# Placa_Base_Blue_Pill.net
KiCad netlist of a schematic drawn in Altium Designer
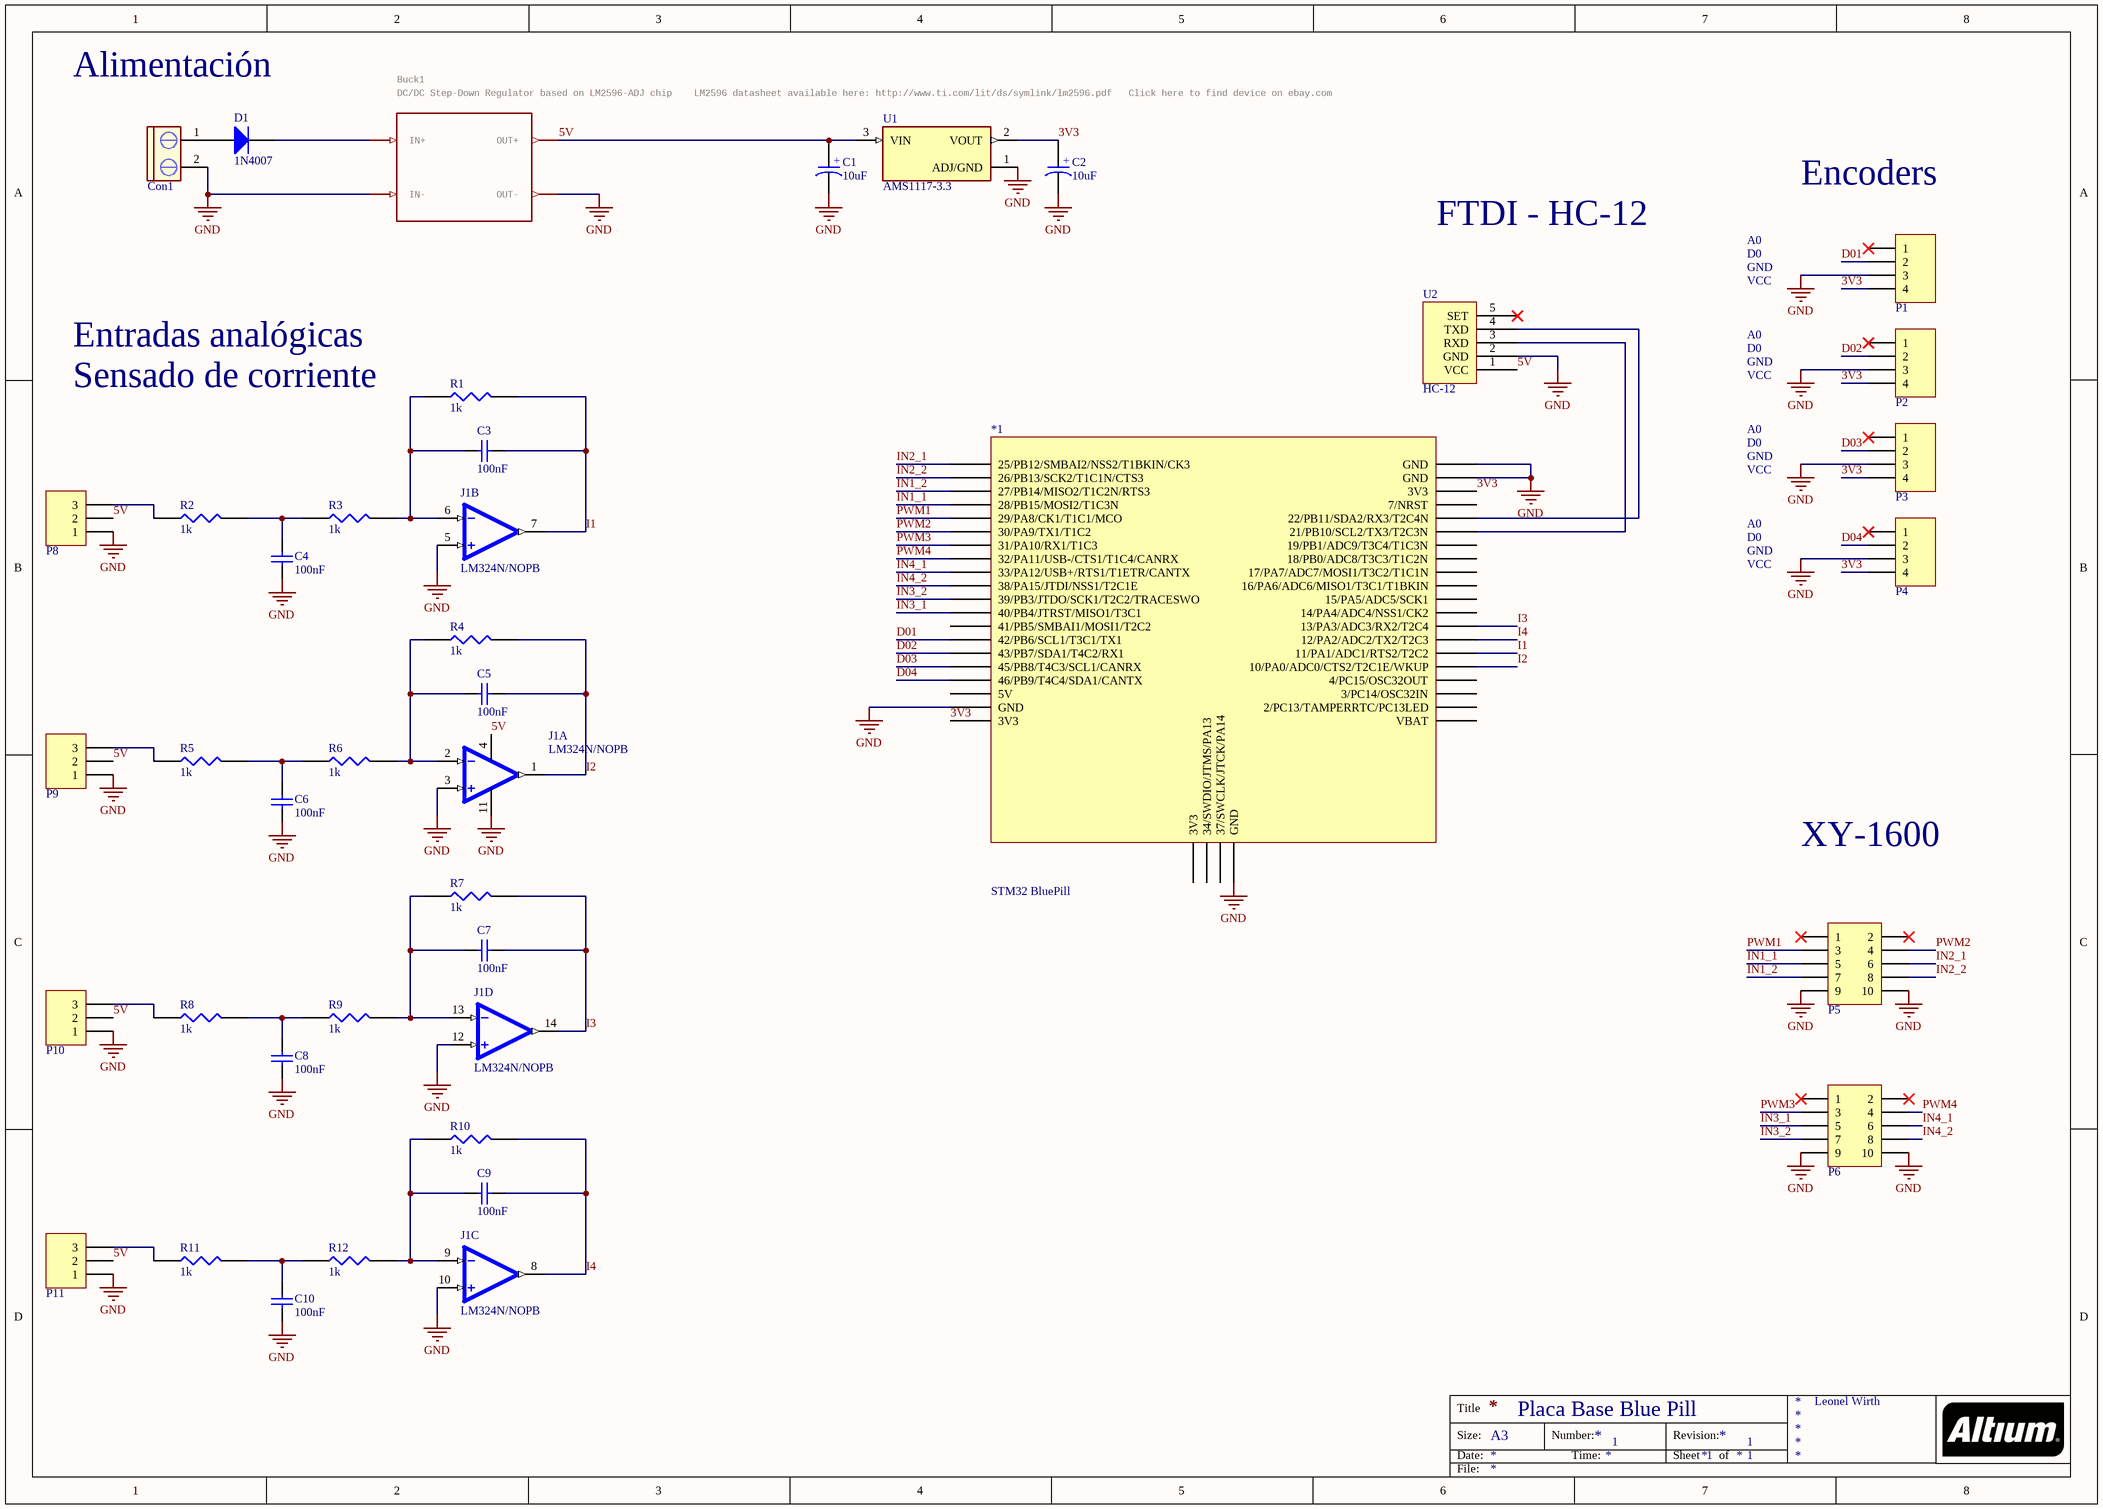
[diagram p0: Placa Base Blue Pill.SchDoc]

(export (version "E")
  (design (tool "Eeschema 10.0.6"))
  (components
    (comp (ref "*1")
      (value "STM32 BluePill")
      (footprint "STM32 BluePill")
      (libsource (lib "LeoLib2.0") (part "STM32 BluePill"))
    )
    (comp (ref "Buck1")
      (value "DC/DC Step-Down Regulator based on LM2596-ADJ chip    LM2596 datasheet available here: http://www.ti.com/lit/ds/symlink/lm2596.pdf   Click here to find device on ebay.com")
      (footprint "DC-DC-STEP-DOWN-LM2596")
      (description "Step Down")
      (libsource (lib "LeoLib2.0") (part "DC-DC-STEP-DOWN-LM2596"))
    )
    (comp (ref "C1")
      (value "10uF")
      (footprint "CAPRADIAL 6.3X11 - 10u")
      (description "CAP_AXIAL")
      (fields (field (name "Comment") "CAP- ELECT"))
      (libsource (lib "LeoLib2.0") (part "Capacitor Electrolitico"))
    )
    (comp (ref "C2")
      (value "10uF")
      (footprint "CAPRADIAL 6.3X11 - 10u")
      (description "CAP_AXIAL")
      (fields (field (name "Comment") "CAP- ELECT"))
      (libsource (lib "LeoLib2.0") (part "Capacitor Electrolitico"))
    )
    (comp (ref "C3")
      (value "100nF")
      (footprint "CAP - LENTEJA")
      (description "CAP-100nf")
      (fields (field (name "Comment") "Cap"))
      (libsource (lib "LeoLib2.0") (part "Capacitor Ceramico"))
    )
    (comp (ref "C4")
      (value "100nF")
      (footprint "CAP - LENTEJA")
      (description "CAP-100nf")
      (fields (field (name "Comment") "Cap"))
      (libsource (lib "LeoLib2.0") (part "Capacitor Ceramico"))
    )
    (comp (ref "C5")
      (value "100nF")
      (footprint "CAP - LENTEJA")
      (description "CAP-100nf")
      (fields (field (name "Comment") "Cap"))
      (libsource (lib "LeoLib2.0") (part "Capacitor Ceramico"))
    )
    (comp (ref "C6")
      (value "100nF")
      (footprint "CAP - LENTEJA")
      (description "CAP-100nf")
      (fields (field (name "Comment") "Cap"))
      (libsource (lib "LeoLib2.0") (part "Capacitor Ceramico"))
    )
    (comp (ref "C7")
      (value "100nF")
      (footprint "CAP - LENTEJA")
      (description "CAP-100nf")
      (fields (field (name "Comment") "Cap"))
      (libsource (lib "LeoLib2.0") (part "Capacitor Ceramico"))
    )
    (comp (ref "C8")
      (value "100nF")
      (footprint "CAP - LENTEJA")
      (description "CAP-100nf")
      (fields (field (name "Comment") "Cap"))
      (libsource (lib "LeoLib2.0") (part "Capacitor Ceramico"))
    )
    (comp (ref "C9")
      (value "100nF")
      (footprint "CAP - LENTEJA")
      (description "CAP-100nf")
      (fields (field (name "Comment") "Cap"))
      (libsource (lib "LeoLib2.0") (part "Capacitor Ceramico"))
    )
    (comp (ref "C10")
      (value "100nF")
      (footprint "CAP - LENTEJA")
      (description "CAP-100nf")
      (fields (field (name "Comment") "Cap"))
      (libsource (lib "LeoLib2.0") (part "Capacitor Ceramico"))
    )
    (comp (ref "Con1")
      (value "CON2 pin blue")
      (footprint "BORNE 2P")
      (description "Connector blue screw")
      (libsource (lib "LeoLib2.0") (part "CON2 pin blue"))
    )
    (comp (ref "D1")
      (value "1N4007")
      (footprint "DO - 41")
      (description "1 Amp Diode")
      (libsource (lib "LeoLib2.0") (part "1N4007"))
    )
    (comp (ref "J1")
      (value "LM324N/NOPB")
      (footprint "DIP825W47P254L1917H533Q14")
      (fields (field (name "MF") "{'manufacturer': u'Texas Instruments'}"))
      (libsource (lib "LeoLib2.0") (part "LM324N/NOPB"))
    )
    (comp (ref "P1")
      (value "Header 4")
      (footprint "1X04")
      (description "Header, 4-Pin")
      (fields (field (name "PUBLISHER") "Altium Limited"))
      (libsource (lib "LeoLib2.0") (part "Header 4"))
    )
    (comp (ref "P2")
      (value "Header 4")
      (footprint "1X04")
      (description "Header, 4-Pin")
      (fields (field (name "PUBLISHER") "Altium Limited"))
      (libsource (lib "LeoLib2.0") (part "Header 4"))
    )
    (comp (ref "P3")
      (value "Header 4")
      (footprint "1X04")
      (description "Header, 4-Pin")
      (fields (field (name "PUBLISHER") "Altium Limited"))
      (libsource (lib "LeoLib2.0") (part "Header 4"))
    )
    (comp (ref "P4")
      (value "Header 4")
      (footprint "1X04")
      (description "Header, 4-Pin")
      (fields (field (name "PUBLISHER") "Altium Limited"))
      (libsource (lib "LeoLib2.0") (part "Header 4"))
    )
    (comp (ref "P5")
      (value "Header 5x2")
      (footprint "2x05 header")
      (description "Header, 5-Pin, Dual row")
      (libsource (lib "LeoLib2.0") (part "Header 5x2"))
    )
    (comp (ref "P6")
      (value "Header 5x2")
      (footprint "2x05 header")
      (description "Header, 5-Pin, Dual row")
      (libsource (lib "LeoLib2.0") (part "Header 5x2"))
    )
    (comp (ref "P8")
      (value "Header 3")
      (footprint "1X03")
      (description "Header, 3-Pin")
      (fields (field (name "PUBLISHER") "Altium Limited"))
      (libsource (lib "LeoLib2.0") (part "Header 3"))
    )
    (comp (ref "P9")
      (value "Header 3")
      (footprint "1X03")
      (description "Header, 3-Pin")
      (fields (field (name "PUBLISHER") "Altium Limited"))
      (libsource (lib "LeoLib2.0") (part "Header 3"))
    )
    (comp (ref "P10")
      (value "Header 3")
      (footprint "1X03")
      (description "Header, 3-Pin")
      (fields (field (name "PUBLISHER") "Altium Limited"))
      (libsource (lib "LeoLib2.0") (part "Header 3"))
    )
    (comp (ref "P11")
      (value "Header 3")
      (footprint "1X03")
      (description "Header, 3-Pin")
      (fields (field (name "PUBLISHER") "Altium Limited"))
      (libsource (lib "LeoLib2.0") (part "Header 3"))
    )
    (comp (ref "R1")
      (value "1k")
      (footprint "RES 1/4")
      (description "resistor")
      (libsource (lib "LeoLib2.0") (part "Res"))
    )
    (comp (ref "R2")
      (value "1k")
      (footprint "RES 1/4")
      (description "resistor")
      (libsource (lib "LeoLib2.0") (part "Res"))
    )
    (comp (ref "R3")
      (value "1k")
      (footprint "RES 1/4")
      (description "resistor")
      (libsource (lib "LeoLib2.0") (part "Res"))
    )
    (comp (ref "R4")
      (value "1k")
      (footprint "RES 1/4")
      (description "resistor")
      (libsource (lib "LeoLib2.0") (part "Res"))
    )
    (comp (ref "R5")
      (value "1k")
      (footprint "RES 1/4")
      (description "resistor")
      (libsource (lib "LeoLib2.0") (part "Res"))
    )
    (comp (ref "R6")
      (value "1k")
      (footprint "RES 1/4")
      (description "resistor")
      (libsource (lib "LeoLib2.0") (part "Res"))
    )
    (comp (ref "R7")
      (value "1k")
      (footprint "RES 1/4")
      (description "resistor")
      (libsource (lib "LeoLib2.0") (part "Res"))
    )
    (comp (ref "R8")
      (value "1k")
      (footprint "RES 1/4")
      (description "resistor")
      (libsource (lib "LeoLib2.0") (part "Res"))
    )
    (comp (ref "R9")
      (value "1k")
      (footprint "RES 1/4")
      (description "resistor")
      (libsource (lib "LeoLib2.0") (part "Res"))
    )
    (comp (ref "R10")
      (value "1k")
      (footprint "RES 1/4")
      (description "resistor")
      (libsource (lib "LeoLib2.0") (part "Res"))
    )
    (comp (ref "R11")
      (value "1k")
      (footprint "RES 1/4")
      (description "resistor")
      (libsource (lib "LeoLib2.0") (part "Res"))
    )
    (comp (ref "R12")
      (value "1k")
      (footprint "RES 1/4")
      (description "resistor")
      (libsource (lib "LeoLib2.0") (part "Res"))
    )
    (comp (ref "U1")
      (value "AMS1117-3.3")
      (footprint "SOT229P700X180-4N")
      (description "Sot223/Pkg 1-Amp 3.3-Volt Low Drop Out Voltage Regulatator")
      (fields (field (name "MF") "{'manufacturer': u'NEC'}"))
      (libsource (lib "LeoLib2.0") (part "AMS1117-3.3"))
    )
    (comp (ref "U2") (value "HC-12") (footprint "HC12") (libsource (lib "LeoLib2.0") (part "HC-12")))
  )
  (nets
    (net (code "1") (name "/3V3") (class "Default")
      (node (ref "*1") (pin "25") (pinfunction "3V3_25") (pintype "passive"))
      (node (ref "*1") (pin "3") (pinfunction "3V3_3") (pintype "passive"))
      (node (ref "C2") (pin "1") (pinfunction "1_1") (pintype "passive"))
      (node (ref "P1") (pin "4") (pinfunction "4_4") (pintype "passive"))
      (node (ref "P2") (pin "4") (pinfunction "4_4") (pintype "passive"))
      (node (ref "P3") (pin "4") (pinfunction "4_4") (pintype "passive"))
      (node (ref "P4") (pin "4") (pinfunction "4_4") (pintype "passive"))
      (node (ref "U1") (pin "2") (pinfunction "VOUT_2") (pintype "output"))
    )
    (net (code "2") (name "/5V") (class "Default")
      (node (ref "Buck1") (pin "OUT+") (pinfunction "OUT+_OUT+") (pintype "output"))
      (node (ref "C1") (pin "1") (pinfunction "1_1") (pintype "passive"))
      (node (ref "J1") (pin "4") (pinfunction "V+_4") (pintype "power_in"))
      (node (ref "P10") (pin "2") (pinfunction "2_2") (pintype "passive"))
      (node (ref "P11") (pin "2") (pinfunction "2_2") (pintype "passive"))
      (node (ref "P8") (pin "2") (pinfunction "2_2") (pintype "passive"))
      (node (ref "P9") (pin "2") (pinfunction "2_2") (pintype "passive"))
      (node (ref "U1") (pin "3") (pinfunction "VIN_3") (pintype "input"))
      (node (ref "U2") (pin "1") (pinfunction "VCC_1") (pintype "passive"))
    )
    (net (code "3") (name "/D01") (class "Default")
      (node (ref "*1") (pin "31") (pinfunction "42/PB6/SCL1/T3C1/TX1_31") (pintype "passive"))
      (node (ref "P1") (pin "2") (pinfunction "2_2") (pintype "passive"))
    )
    (net (code "4") (name "/D02") (class "Default")
      (node (ref "*1") (pin "30") (pinfunction "43/PB7/SDA1/T4C2/RX1_30") (pintype "passive"))
      (node (ref "P2") (pin "2") (pinfunction "2_2") (pintype "passive"))
    )
    (net (code "5") (name "/D03") (class "Default")
      (node (ref "*1") (pin "29") (pinfunction "45/PB8/T4C3/SCL1/CANRX_29") (pintype "passive"))
      (node (ref "P3") (pin "2") (pinfunction "2_2") (pintype "passive"))
    )
    (net (code "6") (name "/D04") (class "Default")
      (node (ref "*1") (pin "28") (pinfunction "46/PB9/T4C4/SDA1/CANTX_28") (pintype "passive"))
      (node (ref "P4") (pin "2") (pinfunction "2_2") (pintype "passive"))
    )
    (net (code "7") (name "/I1") (class "Default")
      (node (ref "*1") (pin "15") (pinfunction "11/PA1/ADC1/RTS2/T2C2_15") (pintype "passive"))
      (node (ref "C3") (pin "2") (pinfunction "2_2") (pintype "passive"))
      (node (ref "J1") (pin "7") (pinfunction "2OUT_7") (pintype "output"))
      (node (ref "R1") (pin "2") (pinfunction "2_2") (pintype "passive"))
    )
    (net (code "8") (name "/I2") (class "Default")
      (node (ref "*1") (pin "16") (pinfunction "10/PA0/ADC0/CTS2/T2C1E/WKUP_16") (pintype "passive"))
      (node (ref "C5") (pin "2") (pinfunction "2_2") (pintype "passive"))
      (node (ref "J1") (pin "1") (pinfunction "1OUT_1") (pintype "output"))
      (node (ref "R4") (pin "2") (pinfunction "2_2") (pintype "passive"))
    )
    (net (code "9") (name "/I3") (class "Default")
      (node (ref "*1") (pin "13") (pinfunction "13/PA3/ADC3/RX2/T2C4_13") (pintype "passive"))
      (node (ref "C7") (pin "2") (pinfunction "2_2") (pintype "passive"))
      (node (ref "J1") (pin "14") (pinfunction "4OUT_14") (pintype "output"))
      (node (ref "R7") (pin "2") (pinfunction "2_2") (pintype "passive"))
    )
    (net (code "10") (name "/I4") (class "Default")
      (node (ref "*1") (pin "14") (pinfunction "12/PA2/ADC2/TX2/T2C3_14") (pintype "passive"))
      (node (ref "C9") (pin "2") (pinfunction "2_2") (pintype "passive"))
      (node (ref "J1") (pin "8") (pinfunction "3OUT_8") (pintype "output"))
      (node (ref "R10") (pin "2") (pinfunction "2_2") (pintype "passive"))
    )
    (net (code "11") (name "/IN1_1") (class "Default")
      (node (ref "*1") (pin "41") (pinfunction "28/PB15/MOSI2/T1C3N_41") (pintype "passive"))
      (node (ref "P5") (pin "5") (pinfunction "5_5") (pintype "passive"))
    )
    (net (code "12") (name "/IN1_2") (class "Default")
      (node (ref "*1") (pin "42") (pinfunction "27/PB14/MISO2/T1C2N/RTS3_42") (pintype "passive"))
      (node (ref "P5") (pin "7") (pinfunction "7_7") (pintype "passive"))
    )
    (net (code "13") (name "/IN2_1") (class "Default")
      (node (ref "*1") (pin "44") (pinfunction "25/PB12/SMBAI2/NSS2/T1BKIN/CK3_44") (pintype "passive"))
      (node (ref "P5") (pin "6") (pinfunction "6_6") (pintype "passive"))
    )
    (net (code "14") (name "/IN2_2") (class "Default")
      (node (ref "*1") (pin "43") (pinfunction "26/PB13/SCK2/T1C1N/CTS3_43") (pintype "passive"))
      (node (ref "P5") (pin "8") (pinfunction "8_8") (pintype "passive"))
    )
    (net (code "15") (name "/IN3_1") (class "Default")
      (node (ref "*1") (pin "33") (pinfunction "40/PB4/JTRST/MISO1/T3C1_33") (pintype "passive"))
      (node (ref "P6") (pin "5") (pinfunction "5_5") (pintype "passive"))
    )
    (net (code "16") (name "/IN3_2") (class "Default")
      (node (ref "*1") (pin "34") (pinfunction "39/PB3/JTDO/SCK1/T2C2/TRACESWO_34") (pintype "passive"))
      (node (ref "P6") (pin "7") (pinfunction "7_7") (pintype "passive"))
    )
    (net (code "17") (name "/IN4_1") (class "Default")
      (node (ref "*1") (pin "36") (pinfunction "33/PA12/USB+/RTS1/T1ETR/CANTX_36") (pintype "passive"))
      (node (ref "P6") (pin "6") (pinfunction "6_6") (pintype "passive"))
    )
    (net (code "18") (name "/IN4_2") (class "Default")
      (node (ref "*1") (pin "35") (pinfunction "38/PA15/JTDI/NSS1/T2C1E_35") (pintype "passive"))
      (node (ref "P6") (pin "8") (pinfunction "8_8") (pintype "passive"))
    )
    (net (code "19") (name "/PWM1") (class "Default")
      (node (ref "*1") (pin "40") (pinfunction "29/PA8/CK1/T1C1/MCO_40") (pintype "passive"))
      (node (ref "P5") (pin "3") (pinfunction "3_3") (pintype "passive"))
    )
    (net (code "20") (name "/PWM2") (class "Default")
      (node (ref "*1") (pin "39") (pinfunction "30/PA9/TX1/T1C2_39") (pintype "passive"))
      (node (ref "P5") (pin "4") (pinfunction "4_4") (pintype "passive"))
    )
    (net (code "21") (name "/PWM3") (class "Default")
      (node (ref "*1") (pin "38") (pinfunction "31/PA10/RX1/T1C3_38") (pintype "passive"))
      (node (ref "P6") (pin "3") (pinfunction "3_3") (pintype "passive"))
    )
    (net (code "22") (name "/PWM4") (class "Default")
      (node (ref "*1") (pin "37") (pinfunction "32/PA11/USB-/CTS1/T1C4/CANRX_37") (pintype "passive"))
      (node (ref "P6") (pin "4") (pinfunction "4_4") (pintype "passive"))
    )
    (net (code "23") (name "GND") (class "Default")
      (node (ref "*1") (pin "1") (pinfunction "GND_1") (pintype "passive"))
      (node (ref "*1") (pin "2") (pinfunction "GND_2") (pintype "passive"))
      (node (ref "*1") (pin "21") (pinfunction "GND_21") (pintype "passive"))
      (node (ref "*1") (pin "26") (pinfunction "GND_26") (pintype "passive"))
      (node (ref "Buck1") (pin "IN-") (pinfunction "IN-_IN-") (pintype "input"))
      (node (ref "Buck1") (pin "OUT-") (pinfunction "OUT-_OUT-") (pintype "output"))
      (node (ref "C1") (pin "2") (pinfunction "2_2") (pintype "passive"))
      (node (ref "C10") (pin "1") (pinfunction "1_1") (pintype "passive"))
      (node (ref "C2") (pin "2") (pinfunction "2_2") (pintype "passive"))
      (node (ref "C4") (pin "1") (pinfunction "1_1") (pintype "passive"))
      (node (ref "C6") (pin "1") (pinfunction "1_1") (pintype "passive"))
      (node (ref "C8") (pin "1") (pinfunction "1_1") (pintype "passive"))
      (node (ref "Con1") (pin "2") (pinfunction "2_2") (pintype "passive"))
      (node (ref "J1") (pin "10") (pinfunction "3IN+_10") (pintype "input"))
      (node (ref "J1") (pin "11") (pinfunction "GND_11") (pintype "power_in"))
      (node (ref "J1") (pin "12") (pinfunction "4IN+_12") (pintype "input"))
      (node (ref "J1") (pin "3") (pinfunction "1IN+_3") (pintype "input"))
      (node (ref "J1") (pin "5") (pinfunction "2IN+_5") (pintype "input"))
      (node (ref "P1") (pin "3") (pinfunction "3_3") (pintype "passive"))
      (node (ref "P10") (pin "1") (pinfunction "1_1") (pintype "passive"))
      (node (ref "P11") (pin "1") (pinfunction "1_1") (pintype "passive"))
      (node (ref "P2") (pin "3") (pinfunction "3_3") (pintype "passive"))
      (node (ref "P3") (pin "3") (pinfunction "3_3") (pintype "passive"))
      (node (ref "P4") (pin "3") (pinfunction "3_3") (pintype "passive"))
      (node (ref "P5") (pin "10") (pinfunction "10_10") (pintype "passive"))
      (node (ref "P5") (pin "9") (pinfunction "9_9") (pintype "passive"))
      (node (ref "P6") (pin "10") (pinfunction "10_10") (pintype "passive"))
      (node (ref "P6") (pin "9") (pinfunction "9_9") (pintype "passive"))
      (node (ref "P8") (pin "1") (pinfunction "1_1") (pintype "passive"))
      (node (ref "P9") (pin "1") (pinfunction "1_1") (pintype "passive"))
      (node (ref "U1") (pin "1") (pinfunction "ADJ/GND_1") (pintype "power_in"))
      (node (ref "U2") (pin "2") (pinfunction "GND_2") (pintype "passive"))
    )
    (net (code "24") (name "Net-(*1-21{slash}PB10{slash}SCL2{slash}TX3{slash}T2C3N)") (class "Default")
      (node (ref "*1") (pin "6") (pinfunction "21/PB10/SCL2/TX3/T2C3N_6") (pintype "passive"))
      (node (ref "U2") (pin "3") (pinfunction "RXD_3") (pintype "passive"))
    )
    (net (code "25") (name "Net-(*1-22{slash}PB11{slash}SDA2{slash}RX3{slash}T2C4N)") (class "Default")
      (node (ref "*1") (pin "5") (pinfunction "22/PB11/SDA2/RX3/T2C4N_5") (pintype "passive"))
      (node (ref "U2") (pin "4") (pinfunction "TXD_4") (pintype "passive"))
    )
    (net (code "26") (name "Net-(Buck1-PadIN+)") (class "Default")
      (node (ref "Buck1") (pin "IN+") (pinfunction "IN+_IN+") (pintype "input"))
      (node (ref "D1") (pin "K") (pinfunction "K_K") (pintype "passive"))
    )
    (net (code "27") (name "Net-(C4-Pad2)") (class "Default")
      (node (ref "C4") (pin "2") (pinfunction "2_2") (pintype "passive"))
      (node (ref "R2") (pin "2") (pinfunction "2_2") (pintype "passive"))
      (node (ref "R3") (pin "1") (pinfunction "1_1") (pintype "passive"))
    )
    (net (code "28") (name "Net-(C6-Pad2)") (class "Default")
      (node (ref "C6") (pin "2") (pinfunction "2_2") (pintype "passive"))
      (node (ref "R5") (pin "2") (pinfunction "2_2") (pintype "passive"))
      (node (ref "R6") (pin "1") (pinfunction "1_1") (pintype "passive"))
    )
    (net (code "29") (name "Net-(C8-Pad2)") (class "Default")
      (node (ref "C8") (pin "2") (pinfunction "2_2") (pintype "passive"))
      (node (ref "R8") (pin "2") (pinfunction "2_2") (pintype "passive"))
      (node (ref "R9") (pin "1") (pinfunction "1_1") (pintype "passive"))
    )
    (net (code "30") (name "Net-(C10-Pad2)") (class "Default")
      (node (ref "C10") (pin "2") (pinfunction "2_2") (pintype "passive"))
      (node (ref "R11") (pin "2") (pinfunction "2_2") (pintype "passive"))
      (node (ref "R12") (pin "1") (pinfunction "1_1") (pintype "passive"))
    )
    (net (code "31") (name "Net-(Con1-Pad1)") (class "Default")
      (node (ref "Con1") (pin "1") (pinfunction "1_1") (pintype "passive"))
      (node (ref "D1") (pin "A") (pinfunction "A_A") (pintype "passive"))
    )
    (net (code "32") (name "Net-(J1A-1IN-)") (class "Default")
      (node (ref "C5") (pin "1") (pinfunction "1_1") (pintype "passive"))
      (node (ref "J1") (pin "2") (pinfunction "1IN-_2") (pintype "input"))
      (node (ref "R4") (pin "1") (pinfunction "1_1") (pintype "passive"))
      (node (ref "R6") (pin "2") (pinfunction "2_2") (pintype "passive"))
    )
    (net (code "33") (name "Net-(J1B-2IN-)") (class "Default")
      (node (ref "C3") (pin "1") (pinfunction "1_1") (pintype "passive"))
      (node (ref "J1") (pin "6") (pinfunction "2IN-_6") (pintype "input"))
      (node (ref "R1") (pin "1") (pinfunction "1_1") (pintype "passive"))
      (node (ref "R3") (pin "2") (pinfunction "2_2") (pintype "passive"))
    )
    (net (code "34") (name "Net-(J1C-3IN-)") (class "Default")
      (node (ref "C9") (pin "1") (pinfunction "1_1") (pintype "passive"))
      (node (ref "J1") (pin "9") (pinfunction "3IN-_9") (pintype "input"))
      (node (ref "R10") (pin "1") (pinfunction "1_1") (pintype "passive"))
      (node (ref "R12") (pin "2") (pinfunction "2_2") (pintype "passive"))
    )
    (net (code "35") (name "Net-(J1D-4IN-)") (class "Default")
      (node (ref "C7") (pin "1") (pinfunction "1_1") (pintype "passive"))
      (node (ref "J1") (pin "13") (pinfunction "4IN-_13") (pintype "input"))
      (node (ref "R7") (pin "1") (pinfunction "1_1") (pintype "passive"))
      (node (ref "R9") (pin "2") (pinfunction "2_2") (pintype "passive"))
    )
    (net (code "36") (name "Net-(P8-Pad3)") (class "Default")
      (node (ref "P8") (pin "3") (pinfunction "3_3") (pintype "passive"))
      (node (ref "R2") (pin "1") (pinfunction "1_1") (pintype "passive"))
    )
    (net (code "37") (name "Net-(P9-Pad3)") (class "Default")
      (node (ref "P9") (pin "3") (pinfunction "3_3") (pintype "passive"))
      (node (ref "R5") (pin "1") (pinfunction "1_1") (pintype "passive"))
    )
    (net (code "38") (name "Net-(P10-Pad3)") (class "Default")
      (node (ref "P10") (pin "3") (pinfunction "3_3") (pintype "passive"))
      (node (ref "R8") (pin "1") (pinfunction "1_1") (pintype "passive"))
    )
    (net (code "39") (name "Net-(P11-Pad3)") (class "Default")
      (node (ref "P11") (pin "3") (pinfunction "3_3") (pintype "passive"))
      (node (ref "R11") (pin "1") (pinfunction "1_1") (pintype "passive"))
    )
    (net (code "40") (name "unconnected-(*1-2{slash}PC13{slash}TAMPERRTC{slash}PC13LED-Pad19)") (class "Default")
      (node (ref "*1") (pin "19") (pinfunction "2/PC13/TAMPERRTC/PC13LED_19") (pintype "passive"))
    )
    (net (code "41") (name "unconnected-(*1-3V3-Pad24)") (class "Default")
      (node (ref "*1") (pin "24") (pinfunction "3V3_24") (pintype "passive"))
    )
    (net (code "42") (name "unconnected-(*1-3{slash}PC14{slash}OSC32IN-Pad18)") (class "Default")
      (node (ref "*1") (pin "18") (pinfunction "3/PC14/OSC32IN_18") (pintype "passive"))
    )
    (net (code "43") (name "unconnected-(*1-4{slash}PC15{slash}OSC32OUT-Pad17)") (class "Default")
      (node (ref "*1") (pin "17") (pinfunction "4/PC15/OSC32OUT_17") (pintype "passive"))
    )
    (net (code "44") (name "unconnected-(*1-5V-Pad27)") (class "Default")
      (node (ref "*1") (pin "27") (pinfunction "5V_27") (pintype "passive"))
    )
    (net (code "45") (name "unconnected-(*1-7{slash}NRST-Pad4)") (class "Default")
      (node (ref "*1") (pin "4") (pinfunction "7/NRST_4") (pintype "passive"))
    )
    (net (code "46") (name "unconnected-(*1-14{slash}PA4{slash}ADC4{slash}NSS1{slash}CK2-Pad12)") (class "Default")
      (node (ref "*1") (pin "12") (pinfunction "14/PA4/ADC4/NSS1/CK2_12") (pintype "passive"))
    )
    (net (code "47") (name "unconnected-(*1-15{slash}PA5{slash}ADC5{slash}SCK1-Pad11)") (class "Default")
      (node (ref "*1") (pin "11") (pinfunction "15/PA5/ADC5/SCK1_11") (pintype "passive"))
    )
    (net (code "48") (name "unconnected-(*1-16{slash}PA6{slash}ADC6{slash}MISO1{slash}T3C1{slash}T1BKIN-Pad10)") (class "Default")
      (node (ref "*1") (pin "10") (pinfunction "16/PA6/ADC6/MISO1/T3C1/T1BKIN_10") (pintype "passive"))
    )
    (net (code "49") (name "unconnected-(*1-17{slash}PA7{slash}ADC7{slash}MOSI1{slash}T3C2{slash}T1C1N-Pad9)") (class "Default")
      (node (ref "*1") (pin "9") (pinfunction "17/PA7/ADC7/MOSI1/T3C2/T1C1N_9") (pintype "passive"))
    )
    (net (code "50") (name "unconnected-(*1-18{slash}PB0{slash}ADC8{slash}T3C3{slash}T1C2N-Pad8)") (class "Default")
      (node (ref "*1") (pin "8") (pinfunction "18/PB0/ADC8/T3C3/T1C2N_8") (pintype "passive"))
    )
    (net (code "51") (name "unconnected-(*1-19{slash}PB1{slash}ADC9{slash}T3C4{slash}T1C3N-Pad7)") (class "Default")
      (node (ref "*1") (pin "7") (pinfunction "19/PB1/ADC9/T3C4/T1C3N_7") (pintype "passive"))
    )
    (net (code "52") (name "unconnected-(*1-34{slash}SWDIO{slash}JTMS{slash}PA13-Pad23)") (class "Default")
      (node (ref "*1") (pin "23") (pinfunction "34/SWDIO/JTMS/PA13_23") (pintype "passive"))
    )
    (net (code "53") (name "unconnected-(*1-37{slash}SWCLK{slash}JTCK{slash}PA14-Pad22)") (class "Default")
      (node (ref "*1") (pin "22") (pinfunction "37/SWCLK/JTCK/PA14_22") (pintype "passive"))
    )
    (net (code "54") (name "unconnected-(*1-41{slash}PB5{slash}SMBAI1{slash}MOSI1{slash}T2C2-Pad32)") (class "Default")
      (node (ref "*1") (pin "32") (pinfunction "41/PB5/SMBAI1/MOSI1/T2C2_32") (pintype "passive"))
    )
    (net (code "55") (name "unconnected-(*1-VBAT-Pad20)") (class "Default")
      (node (ref "*1") (pin "20") (pinfunction "VBAT_20") (pintype "passive"))
    )
    (net (code "56") (name "unconnected-(P1-Pad1)") (class "Default")
      (node (ref "P1") (pin "1") (pinfunction "1_1") (pintype "passive+no_connect"))
    )
    (net (code "57") (name "unconnected-(P2-Pad1)") (class "Default")
      (node (ref "P2") (pin "1") (pinfunction "1_1") (pintype "passive+no_connect"))
    )
    (net (code "58") (name "unconnected-(P3-Pad1)") (class "Default")
      (node (ref "P3") (pin "1") (pinfunction "1_1") (pintype "passive+no_connect"))
    )
    (net (code "59") (name "unconnected-(P4-Pad1)") (class "Default")
      (node (ref "P4") (pin "1") (pinfunction "1_1") (pintype "passive+no_connect"))
    )
    (net (code "60") (name "unconnected-(P5-Pad1)") (class "Default")
      (node (ref "P5") (pin "1") (pinfunction "1_1") (pintype "passive+no_connect"))
    )
    (net (code "61") (name "unconnected-(P5-Pad2)") (class "Default")
      (node (ref "P5") (pin "2") (pinfunction "2_2") (pintype "passive+no_connect"))
    )
    (net (code "62") (name "unconnected-(P6-Pad1)") (class "Default")
      (node (ref "P6") (pin "1") (pinfunction "1_1") (pintype "passive+no_connect"))
    )
    (net (code "63") (name "unconnected-(P6-Pad2)") (class "Default")
      (node (ref "P6") (pin "2") (pinfunction "2_2") (pintype "passive+no_connect"))
    )
    (net (code "64") (name "unconnected-(U2-SET-Pad5)") (class "Default")
      (node (ref "U2") (pin "5") (pinfunction "SET_5") (pintype "passive+no_connect"))
    )
  )
)
